# Misc.net
KiCad netlist of a schematic drawn in Altium Designer
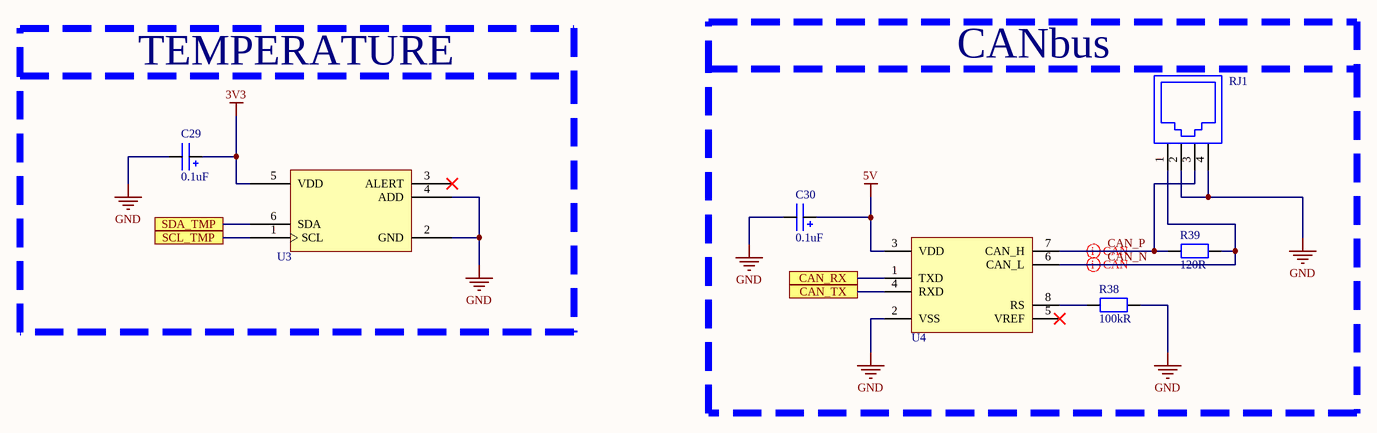
[diagram p0: Misc.SchDoc]

(export (version "E")
  (design (tool "Eeschema 10.0.6"))
  (components
    (comp (ref "C29")
      (value "0.1uF")
      (footprint "CAP 0603")
      (description "Multilayer Ceramic Capacitor")
      (fields (field (name "Comment") "CAP 0603"))
      (libsource (lib "Kaptanyums Lib") (part "CAP 0603"))
    )
    (comp (ref "C30")
      (value "0.1uF")
      (footprint "CAP 0603")
      (description "Multilayer Ceramic Capacitor")
      (fields (field (name "Comment") "CAP 0603"))
      (libsource (lib "Kaptanyums Lib") (part "CAP 0603"))
    )
    (comp (ref "R38")
      (value "100kR")
      (footprint "RESISTOR 0603")
      (description "SMD Chip Resistor")
      (fields (field (name "Comment") "RES 0603"))
      (libsource (lib "Kaptanyums Lib") (part "RES 0603"))
    )
    (comp (ref "R39")
      (value "120R")
      (footprint "RESISTOR 0603")
      (description "SMD Chip Resistor")
      (fields (field (name "Comment") "RES 0603"))
      (libsource (lib "Kaptanyums Lib") (part "RES 0603"))
    )
    (comp (ref "RJ1")
      (value "DS1133-03-S60BX")
      (footprint "RJ6P4C")
      (description "RJ11 Jack")
      (libsource (lib "Kaptanyums Lib") (part "RJ11"))
    )
    (comp (ref "U3")
      (value "TMP112AIDRLT")
      (footprint "SOT563")
      (description "Temp Sensor")
      (libsource (lib "Kaptanyums Lib") (part "TMP112AIDRLT"))
    )
    (comp (ref "U4")
      (value "MCP2551T-I")
      (footprint "SOIC-8")
      (description "CAN Transceiver")
      (libsource (lib "Kaptanyums Lib") (part "MCP2551T-I"))
    )
  )
  (nets
    (net (code "1") (name "/CAN_N") (class "Default")
      (node (ref "R39") (pin "2") (pinfunction "2_2") (pintype "passive"))
      (node (ref "RJ1") (pin "1") (pinfunction "1_1") (pintype "passive"))
      (node (ref "U4") (pin "6") (pinfunction "CAN_L_6") (pintype "passive"))
    )
    (net (code "2") (name "/CAN_P") (class "Default")
      (node (ref "R39") (pin "1") (pinfunction "1_1") (pintype "passive"))
      (node (ref "RJ1") (pin "3") (pinfunction "3_3") (pintype "passive"))
      (node (ref "U4") (pin "7") (pinfunction "CAN_H_7") (pintype "passive"))
    )
    (net (code "3") (name "/CAN_RX") (class "Default")
      (node (ref "U4") (pin "1") (pinfunction "TXD_1") (pintype "passive"))
    )
    (net (code "4") (name "/CAN_TX") (class "Default")
      (node (ref "U4") (pin "4") (pinfunction "RXD_4") (pintype "passive"))
    )
    (net (code "5") (name "/SCL_TMP") (class "Default")
      (node (ref "U3") (pin "1") (pinfunction "SCL_1") (pintype "passive"))
    )
    (net (code "6") (name "/SDA_TMP") (class "Default")
      (node (ref "U3") (pin "6") (pinfunction "SDA_6") (pintype "passive"))
    )
    (net (code "7") (name "3V3") (class "Default")
      (node (ref "C29") (pin "1") (pinfunction "1_1") (pintype "passive"))
      (node (ref "U3") (pin "5") (pinfunction "VDD_5") (pintype "passive"))
    )
    (net (code "8") (name "5V") (class "Default")
      (node (ref "C30") (pin "1") (pinfunction "1_1") (pintype "passive"))
      (node (ref "U4") (pin "3") (pinfunction "VDD_3") (pintype "passive"))
    )
    (net (code "9") (name "GND") (class "Default")
      (node (ref "C29") (pin "2") (pinfunction "2_2") (pintype "passive"))
      (node (ref "C30") (pin "2") (pinfunction "2_2") (pintype "passive"))
      (node (ref "R38") (pin "1") (pinfunction "1_1") (pintype "passive"))
      (node (ref "RJ1") (pin "2") (pinfunction "2_2") (pintype "passive"))
      (node (ref "RJ1") (pin "4") (pinfunction "4_4") (pintype "passive"))
      (node (ref "U3") (pin "2") (pinfunction "GND_2") (pintype "passive"))
      (node (ref "U3") (pin "4") (pinfunction "ADD_4") (pintype "passive"))
      (node (ref "U4") (pin "2") (pinfunction "VSS_2") (pintype "passive"))
    )
    (net (code "10") (name "Net-(U4-RS)") (class "Default")
      (node (ref "R38") (pin "2") (pinfunction "2_2") (pintype "passive"))
      (node (ref "U4") (pin "8") (pinfunction "RS_8") (pintype "passive"))
    )
    (net (code "11") (name "unconnected-(U3-ALERT-Pad3)") (class "Default")
      (node (ref "U3") (pin "3") (pinfunction "ALERT_3") (pintype "passive+no_connect"))
    )
    (net (code "12") (name "unconnected-(U4-VREF-Pad5)") (class "Default")
      (node (ref "U4") (pin "5") (pinfunction "VREF_5") (pintype "passive+no_connect"))
    )
  )
)
